# Audio.net
KiCad netlist of a schematic drawn in Altium Designer
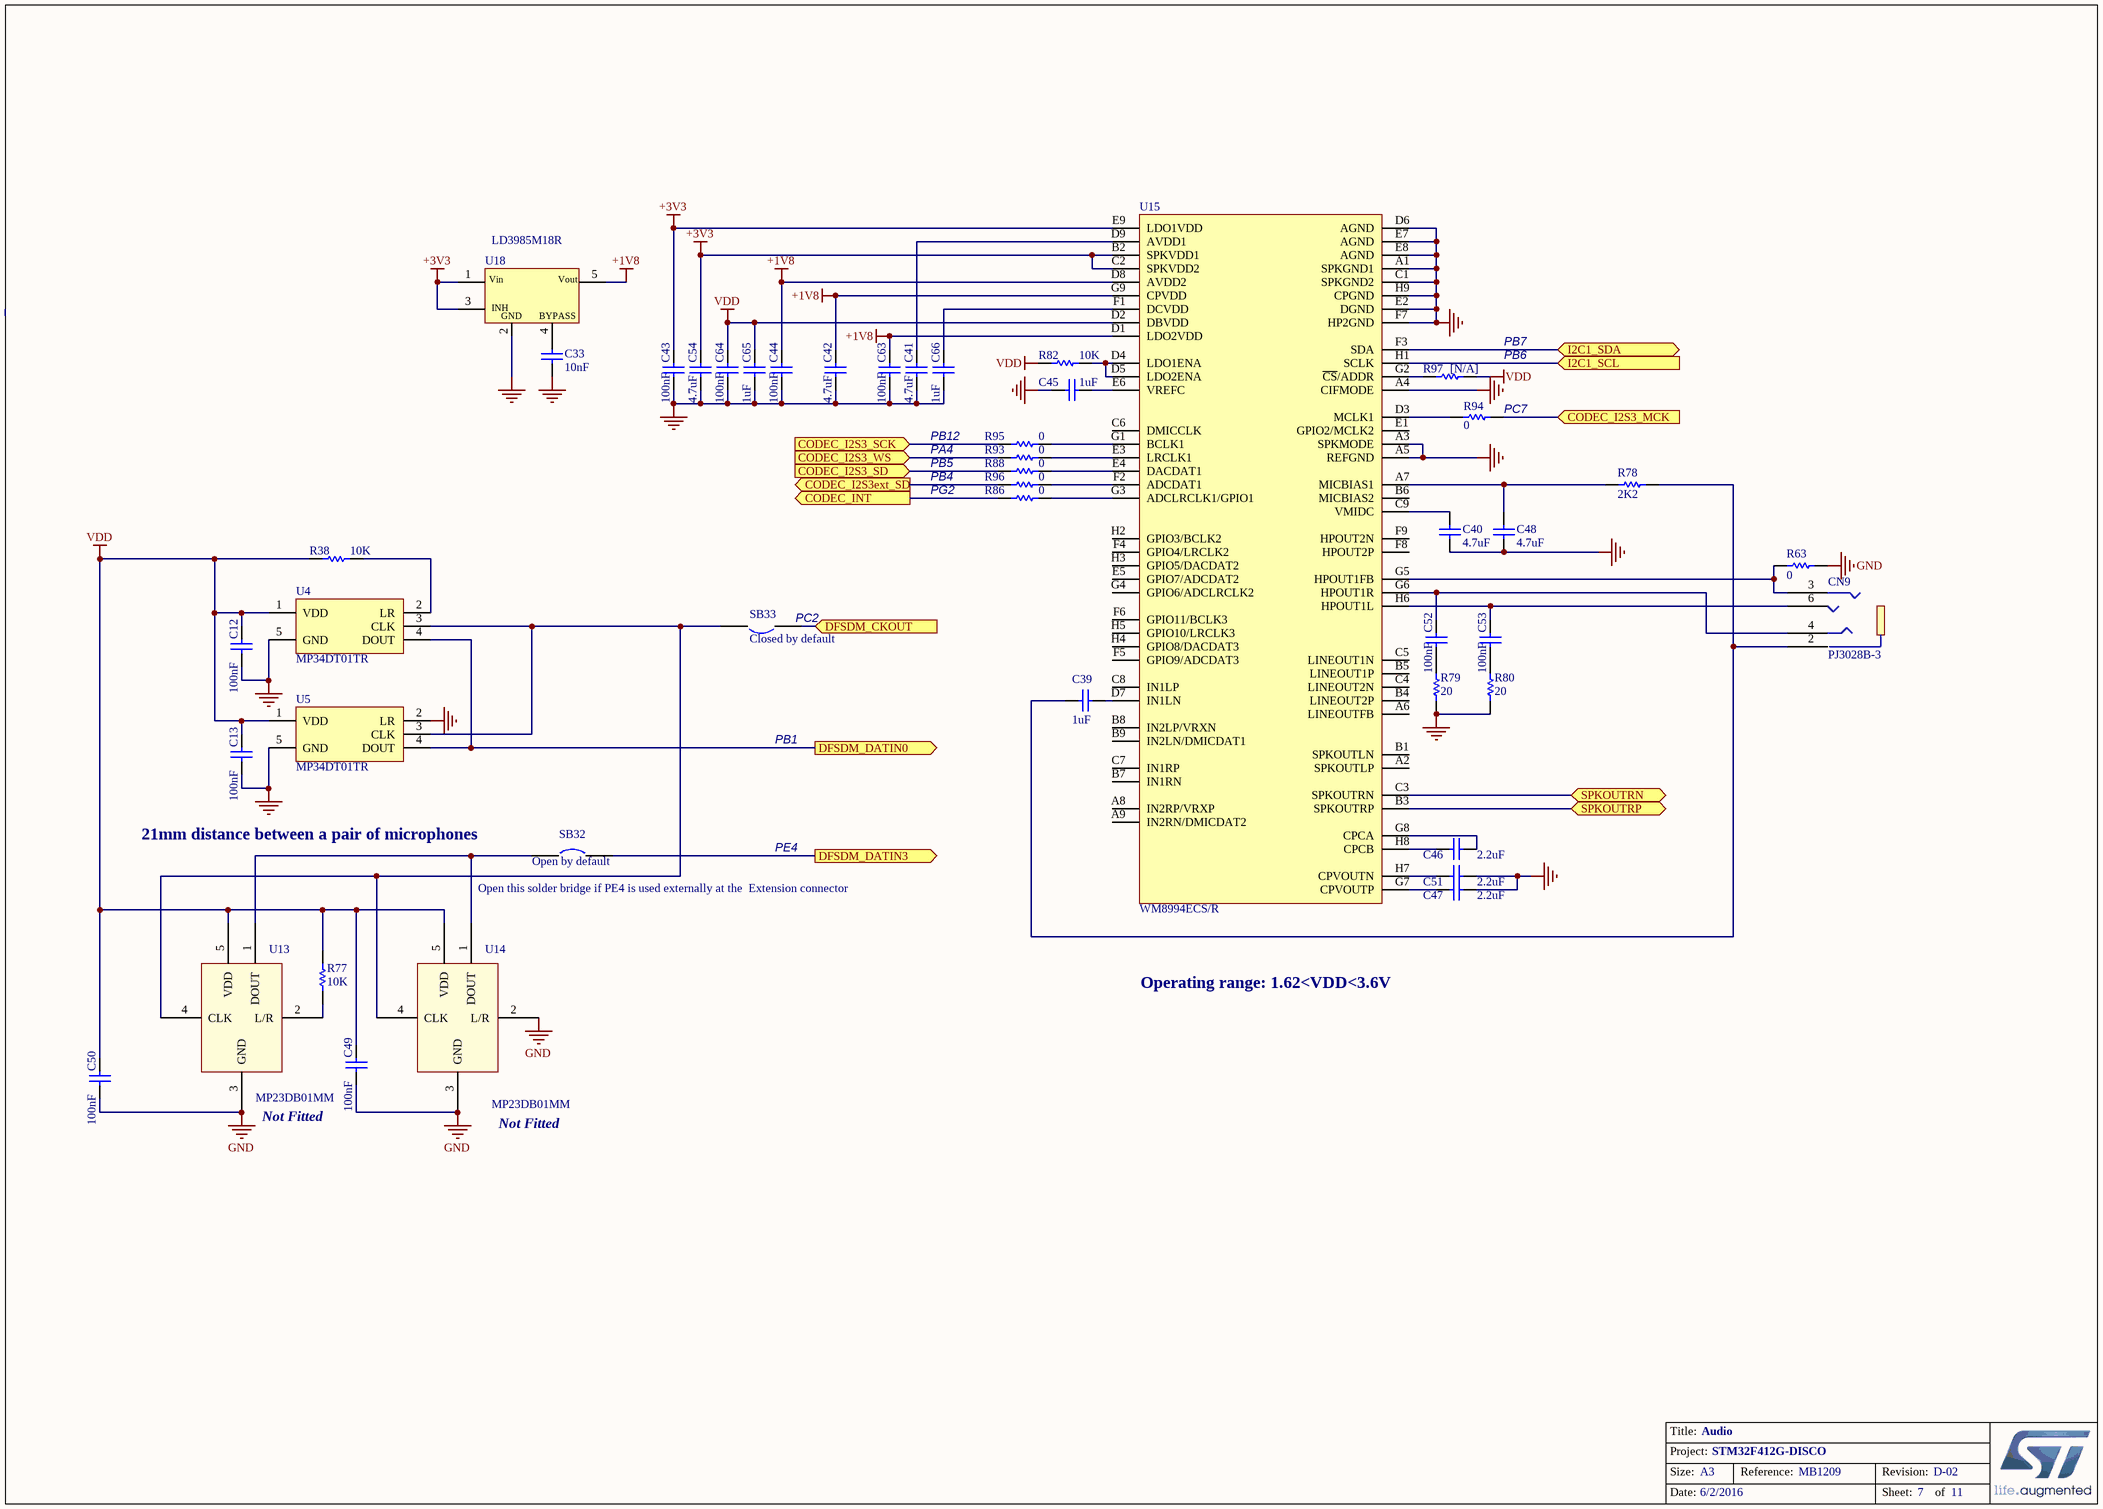
[diagram p0: Audio.SchDoc]

(export (version "E")
  (design (tool "Eeschema 10.0.6"))
  (components
    (comp (ref "C12")
      (value "100nF")
      (footprint "0402C")
      (description "Capacitor")
      (fields (field (name "PUBLISHER") "Altium Limited"))
      (libsource (lib "Miscellaneous Devices") (part "Cap"))
    )
    (comp (ref "C13")
      (value "100nF")
      (footprint "0402C")
      (description "Capacitor")
      (fields (field (name "PUBLISHER") "Altium Limited"))
      (libsource (lib "Miscellaneous Devices") (part "Cap"))
    )
    (comp (ref "C33")
      (value "10nF")
      (footprint "0603C")
      (description "0603  X7R 10NF")
      (fields (field (name "TOLERANCE") "10%"))
      (libsource (lib "MB963_1") (part "CAP SMD 0603  X7R 10000PF 50V 10%"))
    )
    (comp (ref "C39")
      (value "1uF")
      (footprint "0603C")
      (description "Capacitor")
      (fields (field (name "PUBLISHER") "Altium Limited"))
      (libsource (lib "Miscellaneous Devices") (part "CAP"))
    )
    (comp (ref "C40")
      (value "4.7uF")
      (footprint "0603C")
      (description "Capacitor")
      (fields (field (name "PUBLISHER") "Altium Limited"))
      (libsource (lib "Miscellaneous Devices") (part "Cap"))
    )
    (comp (ref "C41")
      (value "4.7uF")
      (footprint "0603C")
      (description "Capacitor")
      (fields (field (name "PUBLISHER") "Altium Limited"))
      (libsource (lib "Miscellaneous Devices") (part "Cap"))
    )
    (comp (ref "C42")
      (value "4.7uF")
      (footprint "0603C")
      (description "Capacitor")
      (fields (field (name "PUBLISHER") "Altium Limited"))
      (libsource (lib "Miscellaneous Devices") (part "Cap"))
    )
    (comp (ref "C43")
      (value "100nF")
      (footprint "0402C")
      (description "Capacitor")
      (fields (field (name "PUBLISHER") "Altium Limited"))
      (libsource (lib "Miscellaneous Devices") (part "Cap"))
    )
    (comp (ref "C44")
      (value "100nF")
      (footprint "0402C")
      (description "Capacitor")
      (fields (field (name "PUBLISHER") "Altium Limited"))
      (libsource (lib "Miscellaneous Devices") (part "Cap"))
    )
    (comp (ref "C45")
      (value "1uF")
      (footprint "0603C")
      (description "Capacitor")
      (fields (field (name "PUBLISHER") "Altium Limited"))
      (libsource (lib "Miscellaneous Devices") (part "CAP"))
    )
    (comp (ref "C46")
      (value "2.2uF")
      (footprint "0603C")
      (description "Capacitor")
      (fields (field (name "PUBLISHER") "Altium Limited"))
      (libsource (lib "Miscellaneous Devices") (part "CAP"))
    )
    (comp (ref "C47")
      (value "2.2uF")
      (footprint "0603C")
      (description "Capacitor")
      (fields (field (name "PUBLISHER") "Altium Limited"))
      (libsource (lib "Miscellaneous Devices") (part "CAP"))
    )
    (comp (ref "C48")
      (value "4.7uF")
      (footprint "0603C")
      (description "Capacitor")
      (fields (field (name "PUBLISHER") "Altium Limited"))
      (libsource (lib "Miscellaneous Devices") (part "Cap"))
    )
    (comp (ref "C49")
      (value "100nF")
      (footprint "0402C")
      (description "Capacitor")
      (fields (field (name "PUBLISHER") "Altium Limited"))
      (libsource (lib "Miscellaneous Devices") (part "Cap"))
    )
    (comp (ref "C50")
      (value "100nF")
      (footprint "0402C")
      (description "Capacitor")
      (fields (field (name "PUBLISHER") "Altium Limited"))
      (libsource (lib "Miscellaneous Devices") (part "Cap"))
    )
    (comp (ref "C51")
      (value "2.2uF")
      (footprint "0603C")
      (description "Capacitor")
      (fields (field (name "PUBLISHER") "Altium Limited"))
      (libsource (lib "Miscellaneous Devices") (part "CAP"))
    )
    (comp (ref "C52")
      (value "100nF")
      (footprint "0402C")
      (description "Capacitor")
      (fields (field (name "PUBLISHER") "Altium Limited"))
      (libsource (lib "Miscellaneous Devices") (part "Cap"))
    )
    (comp (ref "C53")
      (value "100nF")
      (footprint "0402C")
      (description "Capacitor")
      (fields (field (name "PUBLISHER") "Altium Limited"))
      (libsource (lib "Miscellaneous Devices") (part "Cap"))
    )
    (comp (ref "C54")
      (value "4.7uF")
      (footprint "0603C")
      (description "Capacitor")
      (fields (field (name "PUBLISHER") "Altium Limited"))
      (libsource (lib "Miscellaneous Devices") (part "Cap"))
    )
    (comp (ref "C63")
      (value "100nF")
      (footprint "0402C")
      (description "Capacitor")
      (fields (field (name "PUBLISHER") "Altium Limited"))
      (libsource (lib "Miscellaneous Devices") (part "Cap"))
    )
    (comp (ref "C64")
      (value "100nF")
      (footprint "0402C")
      (description "Capacitor")
      (fields (field (name "PUBLISHER") "Altium Limited"))
      (libsource (lib "Miscellaneous Devices") (part "Cap"))
    )
    (comp (ref "C65")
      (value "1uF")
      (footprint "0603C")
      (description "Capacitor")
      (fields (field (name "PUBLISHER") "Altium Limited"))
      (libsource (lib "Miscellaneous Devices") (part "CAP"))
    )
    (comp (ref "C66")
      (value "1uF")
      (footprint "0603C")
      (description "Capacitor")
      (fields (field (name "PUBLISHER") "Altium Limited"))
      (libsource (lib "Miscellaneous Devices") (part "CAP"))
    )
    (comp (ref "CN9") (value "PJ3028B-3") (footprint "PJ3028B") (libsource (lib "MB786") (part "PJ3028B-3")))
    (comp (ref "R38")
      (value "10K")
      (footprint "0402R")
      (description "Resistor")
      (fields (field (name "PUBLISHER") "Altium Limited"))
      (libsource (lib "Miscellaneous Devices") (part "Res1"))
    )
    (comp (ref "R63")
      (value "0")
      (footprint "SB_0603")
      (description "Resistor")
      (fields (field (name "PUBLISHER") "Altium Limited"))
      (libsource (lib "Miscellaneous Devices") (part "Res1"))
    )
    (comp (ref "R77")
      (value "10K")
      (footprint "0402R")
      (description "Resistor")
      (fields (field (name "PUBLISHER") "Altium Limited"))
      (libsource (lib "Miscellaneous Devices") (part "Res1"))
    )
    (comp (ref "R78")
      (value "2K2")
      (footprint "0603R")
      (description "Resistor")
      (fields (field (name "PUBLISHER") "Altium Limited"))
      (libsource (lib "Miscellaneous Devices") (part "Res1"))
    )
    (comp (ref "R79")
      (value "20")
      (footprint "0402R")
      (description "Resistor")
      (fields (field (name "PUBLISHER") "Altium Limited"))
      (libsource (lib "Miscellaneous Devices") (part "Res1"))
    )
    (comp (ref "R80")
      (value "20")
      (footprint "0402R")
      (description "Resistor")
      (fields (field (name "PUBLISHER") "Altium Limited"))
      (libsource (lib "Miscellaneous Devices") (part "Res1"))
    )
    (comp (ref "R82")
      (value "10K")
      (footprint "0402R")
      (description "Resistor")
      (fields (field (name "PUBLISHER") "Altium Limited"))
      (libsource (lib "Miscellaneous Devices") (part "Res1"))
    )
    (comp (ref "R86")
      (value "0")
      (footprint "SB_0603")
      (description "Resistor")
      (fields (field (name "PUBLISHER") "Altium Limited"))
      (libsource (lib "Miscellaneous Devices") (part "Res1"))
    )
    (comp (ref "R88")
      (value "0")
      (footprint "SB_0603")
      (description "Resistor")
      (fields (field (name "PUBLISHER") "Altium Limited"))
      (libsource (lib "Miscellaneous Devices") (part "Res1"))
    )
    (comp (ref "R93")
      (value "0")
      (footprint "SB_0603")
      (description "Resistor")
      (fields (field (name "PUBLISHER") "Altium Limited"))
      (libsource (lib "Miscellaneous Devices") (part "Res1"))
    )
    (comp (ref "R94")
      (value "0")
      (footprint "SB_0603")
      (description "Resistor")
      (fields (field (name "PUBLISHER") "Altium Limited"))
      (libsource (lib "Miscellaneous Devices") (part "Res1"))
    )
    (comp (ref "R95")
      (value "0")
      (footprint "SB_0603")
      (description "Resistor")
      (fields (field (name "PUBLISHER") "Altium Limited"))
      (libsource (lib "Miscellaneous Devices") (part "Res1"))
    )
    (comp (ref "R96")
      (value "0")
      (footprint "SB_0603")
      (description "Resistor")
      (fields (field (name "PUBLISHER") "Altium Limited"))
      (libsource (lib "Miscellaneous Devices") (part "Res1"))
    )
    (comp (ref "R97")
      (value "[N/A]")
      (footprint "0603R")
      (description "Resistor")
      (fields (field (name "PUBLISHER") "Altium Limited"))
      (libsource (lib "Miscellaneous Devices") (part "Res1"))
    )
    (comp (ref "SB32")
      (value "Open by default")
      (footprint "SB_0603")
      (description "Circuit Breaker")
      (fields (field (name "PUBLISHER") "Altium Limited"))
      (libsource (lib "Miscellaneous Devices") (part "Circuit Breaker"))
    )
    (comp (ref "SB33")
      (value "Closed by default")
      (footprint "SB_0603")
      (description "Circuit Breaker")
      (fields (field (name "PUBLISHER") "Altium Limited"))
      (libsource (lib "Miscellaneous Devices") (part "Circuit Breaker"))
    )
    (comp (ref "U4")
      (value "MP34DT01TR")
      (footprint "MP34DT01TR")
      (description "MEMS audio sensor")
      (fields (field (name "PUBLISHER") "Altium Limited"))
      (libsource (lib "mb1045") (part "MP34DT01TR"))
    )
    (comp (ref "U5")
      (value "MP34DT01TR")
      (footprint "MP34DT01TR")
      (description "MEMS audio sensor")
      (fields (field (name "PUBLISHER") "Altium Limited"))
      (libsource (lib "mb1045") (part "MP34DT01TR"))
    )
    (comp (ref "U13")
      (value "MP23DB01MM")
      (footprint "RHLGA5LD")
      (description "MEMS micro")
      (fields (field (name "PUBLISHER") "ST"))
      (libsource (lib "TinyMantaLP1MDisco") (part "MP23DB01MM"))
    )
    (comp (ref "U14")
      (value "MP23DB01MM")
      (footprint "RHLGA5LD")
      (description "MEMS micro")
      (fields (field (name "PUBLISHER") "ST"))
      (libsource (lib "TinyMantaLP1MDisco") (part "MP23DB01MM"))
    )
    (comp (ref "U15")
      (value "WM8994ECS/R")
      (footprint "BGA72_0R5_4R5X4")
      (libsource (lib "mb1045") (part "WM8994ECS/R"))
    )
    (comp (ref "U18")
      (value "LD3985M18R")
      (footprint "SOT23-5")
      (description "Ultra low drop-low noise BiCMOS voltage, regulators low ESR capacitors compatible")
      (libsource (lib "MB1209_2") (part "LD3985M33R"))
    )
  )
  (nets
    (net (code "1") (name "+1V8") (class "Default")
      (node (ref "C42") (pin "1") (pinfunction "1_1") (pintype "passive"))
      (node (ref "C44") (pin "1") (pinfunction "1_1") (pintype "passive"))
      (node (ref "C63") (pin "1") (pinfunction "1_1") (pintype "passive"))
      (node (ref "U15") (pin "D1") (pinfunction "LDO2VDD_D1") (pintype "passive"))
      (node (ref "U15") (pin "D8") (pinfunction "AVDD2_D8") (pintype "passive"))
      (node (ref "U15") (pin "G9") (pinfunction "CPVDD_G9") (pintype "passive"))
      (node (ref "U18") (pin "5") (pinfunction "Vout_5") (pintype "passive"))
    )
    (net (code "2") (name "+3V3") (class "Default")
      (node (ref "C43") (pin "1") (pinfunction "1_1") (pintype "passive"))
      (node (ref "C54") (pin "1") (pinfunction "1_1") (pintype "passive"))
      (node (ref "U15") (pin "B2") (pinfunction "SPKVDD1_B2") (pintype "passive"))
      (node (ref "U15") (pin "C2") (pinfunction "SPKVDD2_C2") (pintype "passive"))
      (node (ref "U15") (pin "E9") (pinfunction "LDO1VDD_E9") (pintype "passive"))
      (node (ref "U18") (pin "1") (pinfunction "Vin_1") (pintype "passive"))
      (node (ref "U18") (pin "3") (pinfunction "CE_3") (pintype "passive"))
    )
    (net (code "3") (name "/CODEC_I2S3_MCK") (class "Default")
      (node (ref "R94") (pin "1") (pinfunction "1_1") (pintype "passive"))
    )
    (net (code "4") (name "/CODEC_I2S3_SCK") (class "Default")
      (node (ref "R95") (pin "2") (pinfunction "2_2") (pintype "passive"))
    )
    (net (code "5") (name "/CODEC_I2S3_SD") (class "Default")
      (node (ref "R88") (pin "2") (pinfunction "2_2") (pintype "passive"))
    )
    (net (code "6") (name "/CODEC_I2S3_WS") (class "Default")
      (node (ref "R93") (pin "2") (pinfunction "2_2") (pintype "passive"))
    )
    (net (code "7") (name "/CODEC_I2S3ext_SD") (class "Default")
      (node (ref "R96") (pin "2") (pinfunction "2_2") (pintype "passive"))
    )
    (net (code "8") (name "/CODEC_INT") (class "Default")
      (node (ref "R86") (pin "2") (pinfunction "2_2") (pintype "passive"))
    )
    (net (code "9") (name "/DFSDM_CKOUT") (class "Default")
      (node (ref "SB33") (pin "1") (pinfunction "1_1") (pintype "passive"))
    )
    (net (code "10") (name "/DFSDM_DATIN0") (class "Default")
      (node (ref "U4") (pin "4") (pinfunction "DOUT_4") (pintype "passive"))
      (node (ref "U5") (pin "4") (pinfunction "DOUT_4") (pintype "passive"))
    )
    (net (code "11") (name "/DFSDM_DATIN3") (class "Default")
      (node (ref "SB32") (pin "2") (pinfunction "2_2") (pintype "passive"))
    )
    (net (code "12") (name "/I2C1_SCL") (class "Default")
      (node (ref "U15") (pin "H1") (pinfunction "SCLK_H1") (pintype "passive"))
    )
    (net (code "13") (name "/I2C1_SDA") (class "Default")
      (node (ref "U15") (pin "F3") (pinfunction "SDA_F3") (pintype "passive"))
    )
    (net (code "14") (name "/SPKOUTRN") (class "Default")
      (node (ref "U15") (pin "C3") (pinfunction "SPKOUTRN_C3") (pintype "passive"))
    )
    (net (code "15") (name "/SPKOUTRP") (class "Default")
      (node (ref "U15") (pin "B3") (pinfunction "SPKOUTRP_B3") (pintype "passive"))
    )
    (net (code "16") (name "GND") (class "Default")
      (node (ref "C12") (pin "2") (pinfunction "2_2") (pintype "passive"))
      (node (ref "C13") (pin "2") (pinfunction "2_2") (pintype "passive"))
      (node (ref "C33") (pin "1") (pinfunction "1_1") (pintype "passive"))
      (node (ref "C40") (pin "1") (pinfunction "1_1") (pintype "passive"))
      (node (ref "C41") (pin "2") (pinfunction "2_2") (pintype "passive"))
      (node (ref "C42") (pin "2") (pinfunction "2_2") (pintype "passive"))
      (node (ref "C43") (pin "2") (pinfunction "2_2") (pintype "passive"))
      (node (ref "C44") (pin "2") (pinfunction "2_2") (pintype "passive"))
      (node (ref "C45") (pin "2") (pinfunction "2_2") (pintype "passive"))
      (node (ref "C47") (pin "2") (pinfunction "2_2") (pintype "passive"))
      (node (ref "C48") (pin "1") (pinfunction "1_1") (pintype "passive"))
      (node (ref "C49") (pin "2") (pinfunction "2_2") (pintype "passive"))
      (node (ref "C50") (pin "2") (pinfunction "2_2") (pintype "passive"))
      (node (ref "C51") (pin "2") (pinfunction "2_2") (pintype "passive"))
      (node (ref "C54") (pin "2") (pinfunction "2_2") (pintype "passive"))
      (node (ref "C63") (pin "2") (pinfunction "2_2") (pintype "passive"))
      (node (ref "C64") (pin "2") (pinfunction "2_2") (pintype "passive"))
      (node (ref "C65") (pin "2") (pinfunction "2_2") (pintype "passive"))
      (node (ref "C66") (pin "2") (pinfunction "2_2") (pintype "passive"))
      (node (ref "R63") (pin "2") (pinfunction "2_2") (pintype "passive"))
      (node (ref "R79") (pin "2") (pinfunction "2_2") (pintype "passive"))
      (node (ref "R80") (pin "2") (pinfunction "2_2") (pintype "passive"))
      (node (ref "U13") (pin "3") (pinfunction "GND_3") (pintype "passive"))
      (node (ref "U14") (pin "2") (pinfunction "L/R_2") (pintype "passive"))
      (node (ref "U14") (pin "3") (pinfunction "GND_3") (pintype "passive"))
      (node (ref "U15") (pin "A1") (pinfunction "SPKGND1_A1") (pintype "passive"))
      (node (ref "U15") (pin "A3") (pinfunction "SPKMODE_A3") (pintype "passive"))
      (node (ref "U15") (pin "A4") (pinfunction "CIFMODE_A4") (pintype "passive"))
      (node (ref "U15") (pin "A5") (pinfunction "REFGND_A5") (pintype "passive"))
      (node (ref "U15") (pin "C1") (pinfunction "SPKGND2_C1") (pintype "passive"))
      (node (ref "U15") (pin "D6") (pinfunction "AGND_D6") (pintype "passive"))
      (node (ref "U15") (pin "E2") (pinfunction "DGND_E2") (pintype "passive"))
      (node (ref "U15") (pin "E7") (pinfunction "AGND_E7") (pintype "passive"))
      (node (ref "U15") (pin "E8") (pinfunction "AGND_E8") (pintype "passive"))
      (node (ref "U15") (pin "F7") (pinfunction "HP2GND_F7") (pintype "passive"))
      (node (ref "U15") (pin "H9") (pinfunction "CPGND_H9") (pintype "passive"))
      (node (ref "U18") (pin "2") (pinfunction "GND_2") (pintype "passive"))
      (node (ref "U4") (pin "5") (pinfunction "GND_5") (pintype "passive"))
      (node (ref "U5") (pin "2") (pinfunction "LR_2") (pintype "passive"))
      (node (ref "U5") (pin "5") (pinfunction "GND_5") (pintype "passive"))
    )
    (net (code "17") (name "Net-(C39-Pad2)") (class "Default")
      (node (ref "C39") (pin "2") (pinfunction "2_2") (pintype "passive"))
      (node (ref "CN9") (pin "2") (pintype "passive"))
      (node (ref "R78") (pin "2") (pinfunction "2_2") (pintype "passive"))
    )
    (net (code "18") (name "Net-(C52-Pad2)") (class "Default")
      (node (ref "C52") (pin "2") (pinfunction "2_2") (pintype "passive"))
      (node (ref "R79") (pin "1") (pinfunction "1_1") (pintype "passive"))
    )
    (net (code "19") (name "Net-(C53-Pad2)") (class "Default")
      (node (ref "C53") (pin "2") (pinfunction "2_2") (pintype "passive"))
      (node (ref "R80") (pin "1") (pinfunction "1_1") (pintype "passive"))
    )
    (net (code "20") (name "Net-(U4-LR)") (class "Default")
      (node (ref "R38") (pin "1") (pinfunction "1_1") (pintype "passive"))
      (node (ref "U4") (pin "2") (pinfunction "LR_2") (pintype "passive"))
    )
    (net (code "21") (name "Net-(U13-CLK)") (class "Default")
      (node (ref "SB33") (pin "2") (pinfunction "2_2") (pintype "passive"))
      (node (ref "U13") (pin "4") (pinfunction "CLK_4") (pintype "passive"))
      (node (ref "U14") (pin "4") (pinfunction "CLK_4") (pintype "passive"))
      (node (ref "U4") (pin "3") (pinfunction "CLK_3") (pintype "passive"))
      (node (ref "U5") (pin "3") (pinfunction "CLK_3") (pintype "passive"))
    )
    (net (code "22") (name "Net-(U13-DOUT)") (class "Default")
      (node (ref "SB32") (pin "1") (pinfunction "1_1") (pintype "passive"))
      (node (ref "U13") (pin "1") (pinfunction "DOUT_1") (pintype "passive"))
      (node (ref "U14") (pin "1") (pinfunction "DOUT_1") (pintype "passive"))
    )
    (net (code "23") (name "Net-(U13-L{slash}R)") (class "Default")
      (node (ref "R77") (pin "2") (pinfunction "2_2") (pintype "passive"))
      (node (ref "U13") (pin "2") (pinfunction "L/R_2") (pintype "passive"))
    )
    (net (code "24") (name "Net-(U15-ADCDAT1)") (class "Default")
      (node (ref "R96") (pin "1") (pinfunction "1_1") (pintype "passive"))
      (node (ref "U15") (pin "F2") (pinfunction "ADCDAT1_F2") (pintype "passive"))
    )
    (net (code "25") (name "Net-(U15-ADCLRCLK1{slash}GPIO1)") (class "Default")
      (node (ref "R86") (pin "1") (pinfunction "1_1") (pintype "passive"))
      (node (ref "U15") (pin "G3") (pinfunction "ADCLRCLK1/GPIO1_G3") (pintype "passive"))
    )
    (net (code "26") (name "Net-(U15-AVDD1)") (class "Default")
      (node (ref "C41") (pin "1") (pinfunction "1_1") (pintype "passive"))
      (node (ref "U15") (pin "D9") (pinfunction "AVDD1_D9") (pintype "passive"))
    )
    (net (code "27") (name "Net-(U15-BCLK1)") (class "Default")
      (node (ref "R95") (pin "1") (pinfunction "1_1") (pintype "passive"))
      (node (ref "U15") (pin "G1") (pinfunction "BCLK1_G1") (pintype "passive"))
    )
    (net (code "28") (name "Net-(U15-CPCA)") (class "Default")
      (node (ref "C46") (pin "2") (pinfunction "2_2") (pintype "passive"))
      (node (ref "U15") (pin "G8") (pinfunction "CPCA_G8") (pintype "passive"))
    )
    (net (code "29") (name "Net-(U15-CPCB)") (class "Default")
      (node (ref "C46") (pin "1") (pinfunction "1_1") (pintype "passive"))
      (node (ref "U15") (pin "H8") (pinfunction "CPCB_H8") (pintype "passive"))
    )
    (net (code "30") (name "Net-(U15-CPVOUTN)") (class "Default")
      (node (ref "C51") (pin "1") (pinfunction "1_1") (pintype "passive"))
      (node (ref "U15") (pin "H7") (pinfunction "CPVOUTN_H7") (pintype "passive"))
    )
    (net (code "31") (name "Net-(U15-CPVOUTP)") (class "Default")
      (node (ref "C47") (pin "1") (pinfunction "1_1") (pintype "passive"))
      (node (ref "U15") (pin "G7") (pinfunction "CPVOUTP_G7") (pintype "passive"))
    )
    (net (code "32") (name "Net-(U15-DACDAT1)") (class "Default")
      (node (ref "R88") (pin "1") (pinfunction "1_1") (pintype "passive"))
      (node (ref "U15") (pin "E4") (pinfunction "DACDAT1_E4") (pintype "passive"))
    )
    (net (code "33") (name "Net-(U15-DCVDD)") (class "Default")
      (node (ref "C66") (pin "1") (pinfunction "1_1") (pintype "passive"))
      (node (ref "U15") (pin "F1") (pinfunction "DCVDD_F1") (pintype "passive"))
    )
    (net (code "34") (name "Net-(U15-HPOUT1FB)") (class "Default")
      (node (ref "CN9") (pin "3") (pintype "passive"))
      (node (ref "R63") (pin "1") (pinfunction "1_1") (pintype "passive"))
      (node (ref "U15") (pin "G5") (pinfunction "HPOUT1FB_G5") (pintype "passive"))
    )
    (net (code "35") (name "Net-(U15-HPOUT1L)") (class "Default")
      (node (ref "C53") (pin "1") (pinfunction "1_1") (pintype "passive"))
      (node (ref "CN9") (pin "6") (pintype "passive"))
      (node (ref "U15") (pin "H6") (pinfunction "HPOUT1L_H6") (pintype "passive"))
    )
    (net (code "36") (name "Net-(U15-HPOUT1R)") (class "Default")
      (node (ref "C52") (pin "1") (pinfunction "1_1") (pintype "passive"))
      (node (ref "CN9") (pin "4") (pintype "passive"))
      (node (ref "U15") (pin "G6") (pinfunction "HPOUT1R_G6") (pintype "passive"))
    )
    (net (code "37") (name "Net-(U15-IN1LN)") (class "Default")
      (node (ref "C39") (pin "1") (pinfunction "1_1") (pintype "passive"))
      (node (ref "U15") (pin "D7") (pinfunction "IN1LN_D7") (pintype "passive"))
    )
    (net (code "38") (name "Net-(U15-LDO1ENA)") (class "Default")
      (node (ref "R82") (pin "1") (pinfunction "1_1") (pintype "passive"))
      (node (ref "U15") (pin "D4") (pinfunction "LDO1ENA_D4") (pintype "passive"))
      (node (ref "U15") (pin "D5") (pinfunction "LDO2ENA_D5") (pintype "passive"))
    )
    (net (code "39") (name "Net-(U15-LRCLK1)") (class "Default")
      (node (ref "R93") (pin "1") (pinfunction "1_1") (pintype "passive"))
      (node (ref "U15") (pin "E3") (pinfunction "LRCLK1_E3") (pintype "passive"))
    )
    (net (code "40") (name "Net-(U15-MCLK1)") (class "Default")
      (node (ref "R94") (pin "2") (pinfunction "2_2") (pintype "passive"))
      (node (ref "U15") (pin "D3") (pinfunction "MCLK1_D3") (pintype "passive"))
    )
    (net (code "41") (name "Net-(U15-MICBIAS1)") (class "Default")
      (node (ref "C48") (pin "2") (pinfunction "2_2") (pintype "passive"))
      (node (ref "R78") (pin "1") (pinfunction "1_1") (pintype "passive"))
      (node (ref "U15") (pin "A7") (pinfunction "MICBIAS1_A7") (pintype "passive"))
    )
    (net (code "42") (name "Net-(U15-VMIDC)") (class "Default")
      (node (ref "C40") (pin "2") (pinfunction "2_2") (pintype "passive"))
      (node (ref "U15") (pin "C9") (pinfunction "VMIDC_C9") (pintype "passive"))
    )
    (net (code "43") (name "Net-(U15-VREFC)") (class "Default")
      (node (ref "C45") (pin "1") (pinfunction "1_1") (pintype "passive"))
      (node (ref "U15") (pin "E6") (pinfunction "VREFC_E6") (pintype "passive"))
    )
    (net (code "44") (name "Net-(U15-~{CS}{slash}ADDR)") (class "Default")
      (node (ref "R97") (pin "2") (pinfunction "2_2") (pintype "passive"))
      (node (ref "U15") (pin "G2") (pinfunction "~{CS}/ADDR_G2") (pintype "passive"))
    )
    (net (code "45") (name "Net-(U18-BYPASS)") (class "Default")
      (node (ref "C33") (pin "2") (pinfunction "2_2") (pintype "passive"))
      (node (ref "U18") (pin "4") (pinfunction "BYPASS_4") (pintype "passive"))
    )
    (net (code "46") (name "VDD") (class "Default")
      (node (ref "C12") (pin "1") (pinfunction "1_1") (pintype "passive"))
      (node (ref "C13") (pin "1") (pinfunction "1_1") (pintype "passive"))
      (node (ref "C49") (pin "1") (pinfunction "1_1") (pintype "passive"))
      (node (ref "C50") (pin "1") (pinfunction "1_1") (pintype "passive"))
      (node (ref "C64") (pin "1") (pinfunction "1_1") (pintype "passive"))
      (node (ref "C65") (pin "1") (pinfunction "1_1") (pintype "passive"))
      (node (ref "R38") (pin "2") (pinfunction "2_2") (pintype "passive"))
      (node (ref "R77") (pin "1") (pinfunction "1_1") (pintype "passive"))
      (node (ref "R82") (pin "2") (pinfunction "2_2") (pintype "passive"))
      (node (ref "R97") (pin "1") (pinfunction "1_1") (pintype "passive"))
      (node (ref "U13") (pin "5") (pinfunction "VDD_5") (pintype "passive"))
      (node (ref "U14") (pin "5") (pinfunction "VDD_5") (pintype "passive"))
      (node (ref "U15") (pin "D2") (pinfunction "DBVDD_D2") (pintype "passive"))
      (node (ref "U4") (pin "1") (pinfunction "VDD_1") (pintype "passive"))
      (node (ref "U5") (pin "1") (pinfunction "VDD_1") (pintype "passive"))
    )
    (net (code "47") (name "unconnected-(U15-DMICCLK-PadC6)") (class "Default")
      (node (ref "U15") (pin "C6") (pinfunction "DMICCLK_C6") (pintype "passive"))
    )
    (net (code "48") (name "unconnected-(U15-GPIO2{slash}MCLK2-PadE1)") (class "Default")
      (node (ref "U15") (pin "E1") (pinfunction "GPIO2/MCLK2_E1") (pintype "passive"))
    )
    (net (code "49") (name "unconnected-(U15-GPIO3{slash}BCLK2-PadH2)") (class "Default")
      (node (ref "U15") (pin "H2") (pinfunction "GPIO3/BCLK2_H2") (pintype "passive"))
    )
    (net (code "50") (name "unconnected-(U15-GPIO4{slash}LRCLK2-PadF4)") (class "Default")
      (node (ref "U15") (pin "F4") (pinfunction "GPIO4/LRCLK2_F4") (pintype "passive"))
    )
    (net (code "51") (name "unconnected-(U15-GPIO5{slash}DACDAT2-PadH3)") (class "Default")
      (node (ref "U15") (pin "H3") (pinfunction "GPIO5/DACDAT2_H3") (pintype "passive"))
    )
    (net (code "52") (name "unconnected-(U15-GPIO6{slash}ADCLRCLK2-PadG4)") (class "Default")
      (node (ref "U15") (pin "G4") (pinfunction "GPIO6/ADCLRCLK2_G4") (pintype "passive"))
    )
    (net (code "53") (name "unconnected-(U15-GPIO7{slash}ADCDAT2-PadE5)") (class "Default")
      (node (ref "U15") (pin "E5") (pinfunction "GPIO7/ADCDAT2_E5") (pintype "passive"))
    )
    (net (code "54") (name "unconnected-(U15-GPIO8{slash}DACDAT3-PadH4)") (class "Default")
      (node (ref "U15") (pin "H4") (pinfunction "GPIO8/DACDAT3_H4") (pintype "passive"))
    )
    (net (code "55") (name "unconnected-(U15-GPIO9{slash}ADCDAT3-PadF5)") (class "Default")
      (node (ref "U15") (pin "F5") (pinfunction "GPIO9/ADCDAT3_F5") (pintype "passive"))
    )
    (net (code "56") (name "unconnected-(U15-GPIO10{slash}LRCLK3-PadH5)") (class "Default")
      (node (ref "U15") (pin "H5") (pinfunction "GPIO10/LRCLK3_H5") (pintype "passive"))
    )
    (net (code "57") (name "unconnected-(U15-GPIO11{slash}BCLK3-PadF6)") (class "Default")
      (node (ref "U15") (pin "F6") (pinfunction "GPIO11/BCLK3_F6") (pintype "passive"))
    )
    (net (code "58") (name "unconnected-(U15-HPOUT2N-PadF9)") (class "Default")
      (node (ref "U15") (pin "F9") (pinfunction "HPOUT2N_F9") (pintype "passive"))
    )
    (net (code "59") (name "unconnected-(U15-HPOUT2P-PadF8)") (class "Default")
      (node (ref "U15") (pin "F8") (pinfunction "HPOUT2P_F8") (pintype "passive"))
    )
    (net (code "60") (name "unconnected-(U15-IN1LP-PadC8)") (class "Default")
      (node (ref "U15") (pin "C8") (pinfunction "IN1LP_C8") (pintype "passive"))
    )
    (net (code "61") (name "unconnected-(U15-IN1RN-PadB7)") (class "Default")
      (node (ref "U15") (pin "B7") (pinfunction "IN1RN_B7") (pintype "passive"))
    )
    (net (code "62") (name "unconnected-(U15-IN1RP-PadC7)") (class "Default")
      (node (ref "U15") (pin "C7") (pinfunction "IN1RP_C7") (pintype "passive"))
    )
    (net (code "63") (name "unconnected-(U15-IN2LN{slash}DMICDAT1-PadB9)") (class "Default")
      (node (ref "U15") (pin "B9") (pinfunction "IN2LN/DMICDAT1_B9") (pintype "passive"))
    )
    (net (code "64") (name "unconnected-(U15-IN2LP{slash}VRXN-PadB8)") (class "Default")
      (node (ref "U15") (pin "B8") (pinfunction "IN2LP/VRXN_B8") (pintype "passive"))
    )
    (net (code "65") (name "unconnected-(U15-IN2RN{slash}DMICDAT2-PadA9)") (class "Default")
      (node (ref "U15") (pin "A9") (pinfunction "IN2RN/DMICDAT2_A9") (pintype "passive"))
    )
    (net (code "66") (name "unconnected-(U15-IN2RP{slash}VRXP-PadA8)") (class "Default")
      (node (ref "U15") (pin "A8") (pinfunction "IN2RP/VRXP_A8") (pintype "passive"))
    )
    (net (code "67") (name "unconnected-(U15-LINEOUT1N-PadC5)") (class "Default")
      (node (ref "U15") (pin "C5") (pinfunction "LINEOUT1N_C5") (pintype "passive"))
    )
    (net (code "68") (name "unconnected-(U15-LINEOUT1P-PadB5)") (class "Default")
      (node (ref "U15") (pin "B5") (pinfunction "LINEOUT1P_B5") (pintype "passive"))
    )
    (net (code "69") (name "unconnected-(U15-LINEOUT2N-PadC4)") (class "Default")
      (node (ref "U15") (pin "C4") (pinfunction "LINEOUT2N_C4") (pintype "passive"))
    )
    (net (code "70") (name "unconnected-(U15-LINEOUT2P-PadB4)") (class "Default")
      (node (ref "U15") (pin "B4") (pinfunction "LINEOUT2P_B4") (pintype "passive"))
    )
    (net (code "71") (name "unconnected-(U15-LINEOUTFB-PadA6)") (class "Default")
      (node (ref "U15") (pin "A6") (pinfunction "LINEOUTFB_A6") (pintype "passive"))
    )
    (net (code "72") (name "unconnected-(U15-MICBIAS2-PadB6)") (class "Default")
      (node (ref "U15") (pin "B6") (pinfunction "MICBIAS2_B6") (pintype "passive"))
    )
    (net (code "73") (name "unconnected-(U15-SPKOUTLN-PadB1)") (class "Default")
      (node (ref "U15") (pin "B1") (pinfunction "SPKOUTLN_B1") (pintype "passive"))
    )
    (net (code "74") (name "unconnected-(U15-SPKOUTLP-PadA2)") (class "Default")
      (node (ref "U15") (pin "A2") (pinfunction "SPKOUTLP_A2") (pintype "passive"))
    )
  )
)
